# watch_1v1_connector_breakout.net
KiCad netlist of a schematic drawn in Altium Designer
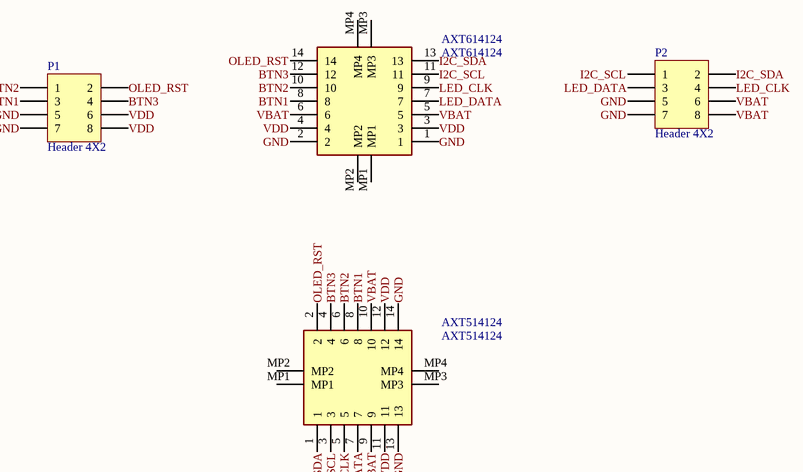
[diagram p0: watch_1v1_connector_breakout.SchDoc]

(export (version "E")
  (design (tool "Eeschema 10.0.6"))
  (components
    (comp (ref "AXT514124")
      (value "AXT514124")
      (footprint "SamacSys:AXT514124")
      (description "Connector")
      (fields (field (name "MOUSER PART NUMBER") "769-AXT514124"))
      (libsource (lib "*") (part "AXT514124"))
    )
    (comp (ref "AXT614124")
      (value "AXT614124")
      (footprint "SamacSys:AXT614124")
      (description "Connector")
      (fields (field (name "MOUSER PART NUMBER") "769-AXT614124"))
      (libsource (lib "*") (part "AXT614124"))
    )
    (comp (ref "P1")
      (value "Header 4X2")
      (footprint "HDR2X4")
      (description "Header, 4-Pin, Dual row")
      (fields (field (name "PUBLISHER") "Altium Limited"))
      (libsource (lib "Miscellaneous Connectors") (part "Header 4X2"))
    )
    (comp (ref "P2")
      (value "Header 4X2")
      (footprint "HDR2X4")
      (description "Header, 4-Pin, Dual row")
      (fields (field (name "PUBLISHER") "Altium Limited"))
      (libsource (lib "Miscellaneous Connectors") (part "Header 4X2"))
    )
  )
  (nets
    (net (code "1") (name "/BTN1") (class "Default")
      (node (ref "AXT514124") (pin "8") (pinfunction "8_8") (pintype "passive"))
      (node (ref "AXT614124") (pin "8") (pinfunction "8_8") (pintype "passive"))
      (node (ref "P1") (pin "3") (pinfunction "3_3") (pintype "passive"))
    )
    (net (code "2") (name "/BTN2") (class "Default")
      (node (ref "AXT514124") (pin "6") (pinfunction "6_6") (pintype "passive"))
      (node (ref "AXT614124") (pin "10") (pinfunction "10_10") (pintype "passive"))
      (node (ref "P1") (pin "1") (pinfunction "1_1") (pintype "passive"))
    )
    (net (code "3") (name "/BTN3") (class "Default")
      (node (ref "AXT514124") (pin "4") (pinfunction "4_4") (pintype "passive"))
      (node (ref "AXT614124") (pin "12") (pinfunction "12_12") (pintype "passive"))
      (node (ref "P1") (pin "4") (pinfunction "4_4") (pintype "passive"))
    )
    (net (code "4") (name "/GND") (class "Default")
      (node (ref "AXT514124") (pin "13") (pinfunction "13_13") (pintype "passive"))
      (node (ref "AXT514124") (pin "14") (pinfunction "14_14") (pintype "passive"))
      (node (ref "AXT614124") (pin "1") (pinfunction "1_1") (pintype "passive"))
      (node (ref "AXT614124") (pin "2") (pinfunction "2_2") (pintype "passive"))
      (node (ref "P1") (pin "5") (pinfunction "5_5") (pintype "passive"))
      (node (ref "P1") (pin "7") (pinfunction "7_7") (pintype "passive"))
      (node (ref "P2") (pin "5") (pinfunction "5_5") (pintype "passive"))
      (node (ref "P2") (pin "7") (pinfunction "7_7") (pintype "passive"))
    )
    (net (code "5") (name "/I2C_SCL") (class "Default")
      (node (ref "AXT514124") (pin "3") (pinfunction "3_3") (pintype "passive"))
      (node (ref "AXT614124") (pin "11") (pinfunction "11_11") (pintype "passive"))
      (node (ref "P2") (pin "1") (pinfunction "1_1") (pintype "passive"))
    )
    (net (code "6") (name "/I2C_SDA") (class "Default")
      (node (ref "AXT514124") (pin "1") (pinfunction "1_1") (pintype "passive"))
      (node (ref "AXT614124") (pin "13") (pinfunction "13_13") (pintype "passive"))
      (node (ref "P2") (pin "2") (pinfunction "2_2") (pintype "passive"))
    )
    (net (code "7") (name "/LED_CLK") (class "Default")
      (node (ref "AXT514124") (pin "5") (pinfunction "5_5") (pintype "passive"))
      (node (ref "AXT614124") (pin "9") (pinfunction "9_9") (pintype "passive"))
      (node (ref "P2") (pin "4") (pinfunction "4_4") (pintype "passive"))
    )
    (net (code "8") (name "/LED_DATA") (class "Default")
      (node (ref "AXT514124") (pin "7") (pinfunction "7_7") (pintype "passive"))
      (node (ref "AXT614124") (pin "7") (pinfunction "7_7") (pintype "passive"))
      (node (ref "P2") (pin "3") (pinfunction "3_3") (pintype "passive"))
    )
    (net (code "9") (name "/OLED_RST") (class "Default")
      (node (ref "AXT514124") (pin "2") (pinfunction "2_2") (pintype "passive"))
      (node (ref "AXT614124") (pin "14") (pinfunction "14_14") (pintype "passive"))
      (node (ref "P1") (pin "2") (pinfunction "2_2") (pintype "passive"))
    )
    (net (code "10") (name "/VBAT") (class "Default")
      (node (ref "AXT514124") (pin "10") (pinfunction "10_10") (pintype "passive"))
      (node (ref "AXT514124") (pin "9") (pinfunction "9_9") (pintype "passive"))
      (node (ref "AXT614124") (pin "5") (pinfunction "5_5") (pintype "passive"))
      (node (ref "AXT614124") (pin "6") (pinfunction "6_6") (pintype "passive"))
      (node (ref "P2") (pin "6") (pinfunction "6_6") (pintype "passive"))
      (node (ref "P2") (pin "8") (pinfunction "8_8") (pintype "passive"))
    )
    (net (code "11") (name "/VDD") (class "Default")
      (node (ref "AXT514124") (pin "11") (pinfunction "11_11") (pintype "passive"))
      (node (ref "AXT514124") (pin "12") (pinfunction "12_12") (pintype "passive"))
      (node (ref "AXT614124") (pin "3") (pinfunction "3_3") (pintype "passive"))
      (node (ref "AXT614124") (pin "4") (pinfunction "4_4") (pintype "passive"))
      (node (ref "P1") (pin "6") (pinfunction "6_6") (pintype "passive"))
      (node (ref "P1") (pin "8") (pinfunction "8_8") (pintype "passive"))
    )
    (net (code "12") (name "unconnected-(AXT514124-PadMP1)") (class "Default")
      (node (ref "AXT514124") (pin "MP1") (pinfunction "MP1_MP1") (pintype "passive"))
    )
    (net (code "13") (name "unconnected-(AXT514124-PadMP2)") (class "Default")
      (node (ref "AXT514124") (pin "MP2") (pinfunction "MP2_MP2") (pintype "passive"))
    )
    (net (code "14") (name "unconnected-(AXT514124-PadMP3)") (class "Default")
      (node (ref "AXT514124") (pin "MP3") (pinfunction "MP3_MP3") (pintype "passive"))
    )
    (net (code "15") (name "unconnected-(AXT514124-PadMP4)") (class "Default")
      (node (ref "AXT514124") (pin "MP4") (pinfunction "MP4_MP4") (pintype "passive"))
    )
    (net (code "16") (name "unconnected-(AXT614124-PadMP1)") (class "Default")
      (node (ref "AXT614124") (pin "MP1") (pinfunction "MP1_MP1") (pintype "passive"))
    )
    (net (code "17") (name "unconnected-(AXT614124-PadMP2)") (class "Default")
      (node (ref "AXT614124") (pin "MP2") (pinfunction "MP2_MP2") (pintype "passive"))
    )
    (net (code "18") (name "unconnected-(AXT614124-PadMP3)") (class "Default")
      (node (ref "AXT614124") (pin "MP3") (pinfunction "MP3_MP3") (pintype "passive"))
    )
    (net (code "19") (name "unconnected-(AXT614124-PadMP4)") (class "Default")
      (node (ref "AXT614124") (pin "MP4") (pinfunction "MP4_MP4") (pintype "passive"))
    )
  )
)
